# Final_Sch.net
KiCad netlist of a schematic drawn in EAGLE
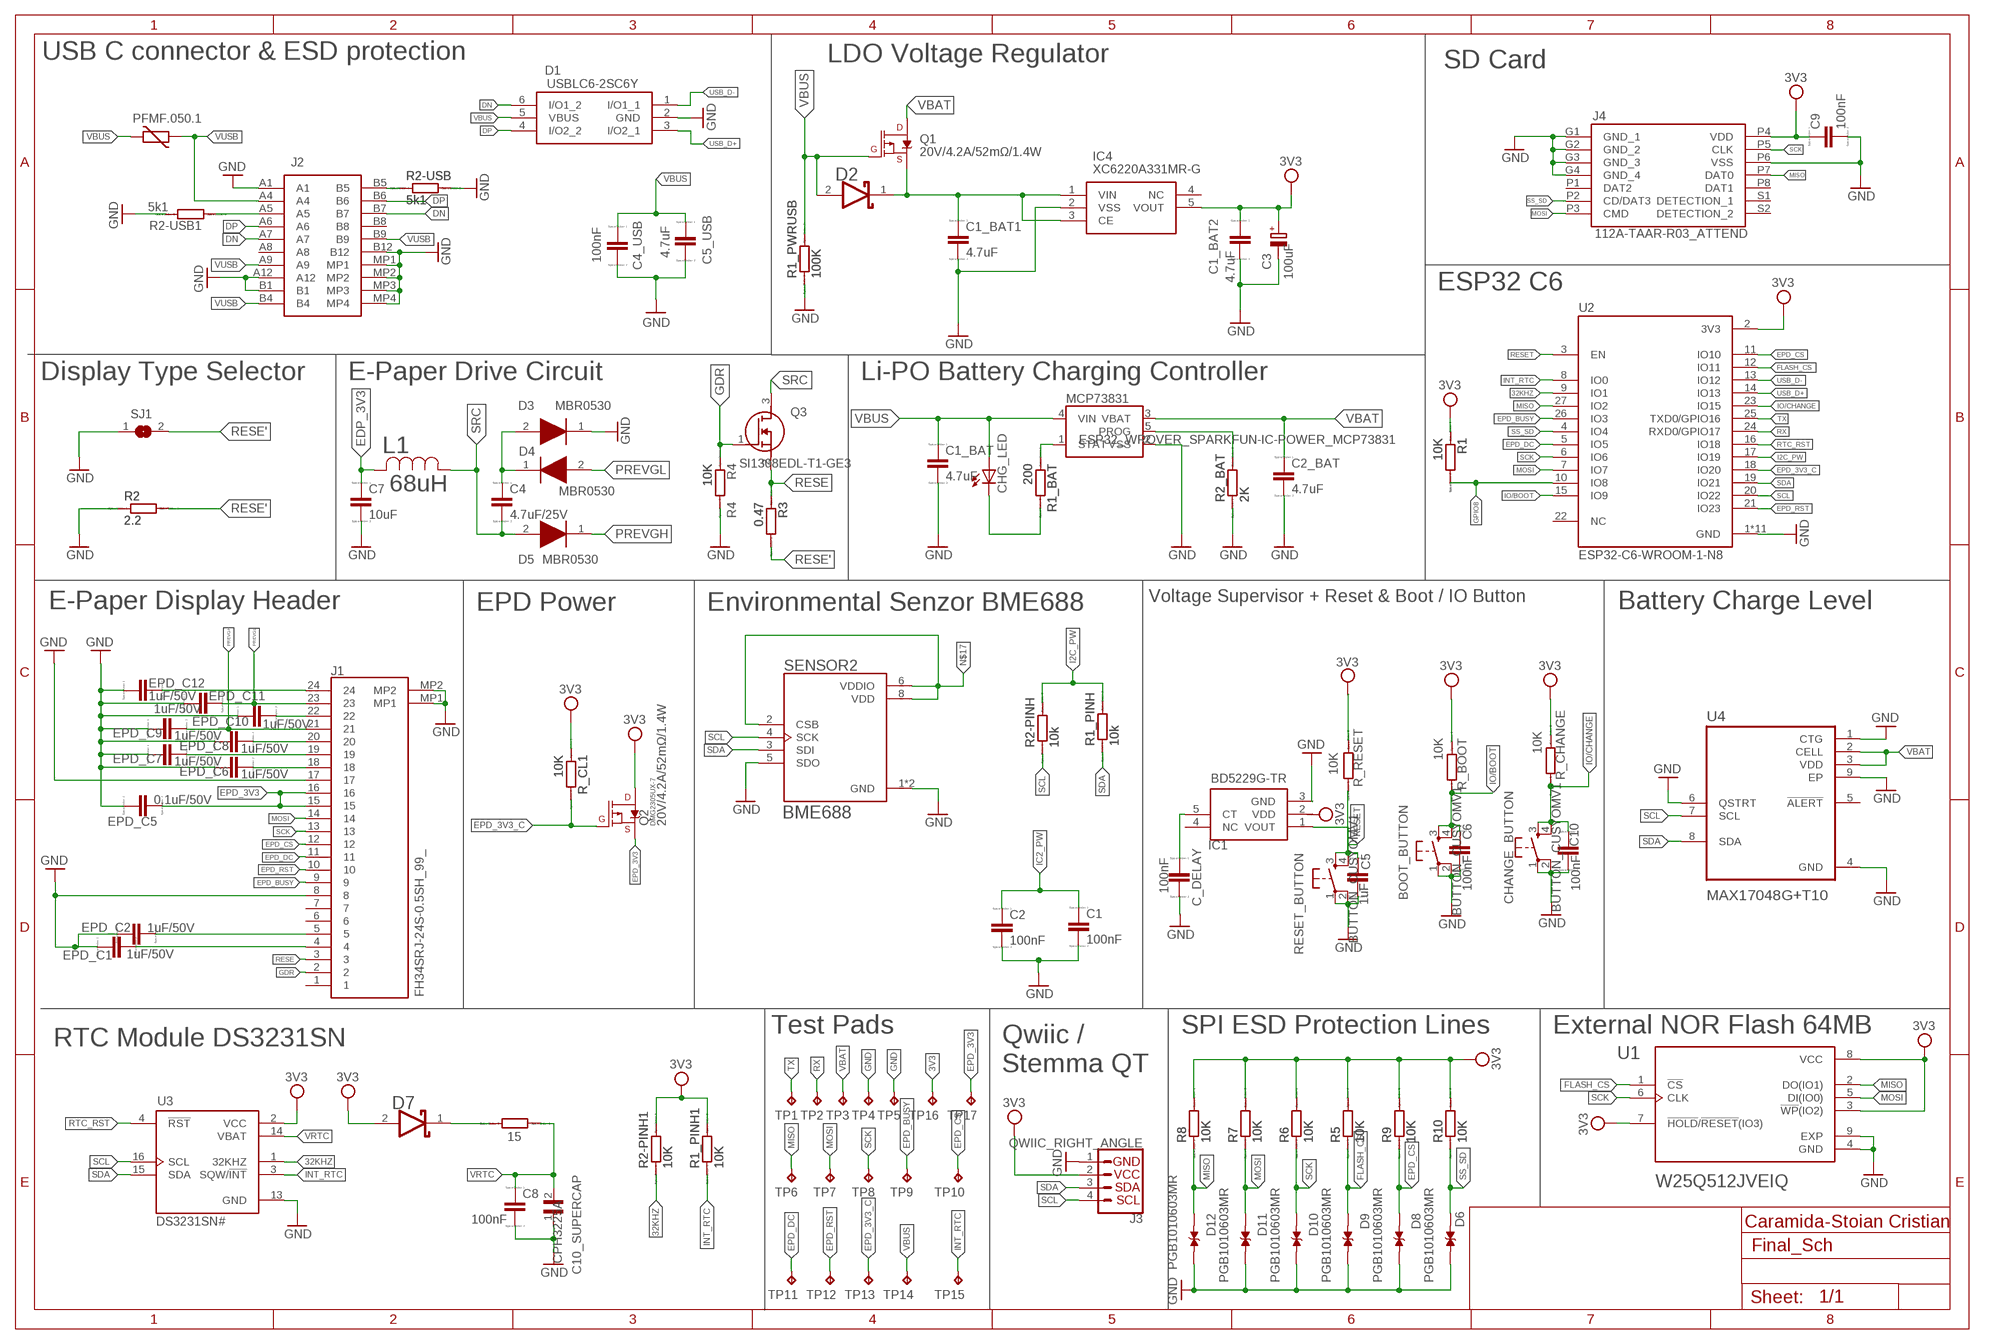
[diagram p0: schematic, sheet 1]

(export (version "E")
  (design (tool "Eeschema 10.0.6"))
  (components
    (comp (ref "BOOT_BUTTON")
      (value "BUTTON_CUSYOMV1")
      (footprint "eagle-import:MYBUTTON")
      (libsource (lib "eagle-import") (part "BUTTON_CUSYOMV1"))
    )
    (comp (ref "C1")
      (value "100nF")
      (footprint "eagle-import:ESP32_WROVER_EAGLE-LTSPICE_C0402")
      (libsource (lib "eagle-import") (part "ESP32_WROVER_EAGLE-LTSPICE_CC0402"))
    )
    (comp (ref "C1_BAT")
      (value "4.7uF")
      (footprint "eagle-import:ESP32_WROVER_EAGLE-LTSPICE_C0402")
      (libsource (lib "eagle-import") (part "ESP32_WROVER_EAGLE-LTSPICE_CC0402"))
    )
    (comp (ref "C1_BAT1")
      (value "4.7uF")
      (footprint "eagle-import:ESP32_WROVER_EAGLE-LTSPICE_C0402")
      (libsource (lib "eagle-import") (part "ESP32_WROVER_EAGLE-LTSPICE_CC0402"))
    )
    (comp (ref "C1_BAT2")
      (value "4.7uF")
      (footprint "eagle-import:ESP32_WROVER_EAGLE-LTSPICE_C0402")
      (libsource (lib "eagle-import") (part "ESP32_WROVER_EAGLE-LTSPICE_CC0402"))
    )
    (comp (ref "C2")
      (value "100nF")
      (footprint "eagle-import:ESP32_WROVER_EAGLE-LTSPICE_C0402")
      (libsource (lib "eagle-import") (part "ESP32_WROVER_EAGLE-LTSPICE_CC0402"))
    )
    (comp (ref "C2_BAT")
      (value "4.7uF")
      (footprint "eagle-import:ESP32_WROVER_EAGLE-LTSPICE_C0402")
      (libsource (lib "eagle-import") (part "ESP32_WROVER_EAGLE-LTSPICE_CC0402"))
    )
    (comp (ref "C3")
      (value "100uF")
      (footprint "eagle-import:RCL_CT3528")
      (libsource (lib "eagle-import") (part "RCL_CPOL-EUCT3528"))
    )
    (comp (ref "C4")
      (value "4.7uF/25V")
      (footprint "eagle-import:ESP32_WROVER_EAGLE-LTSPICE_C0402")
      (libsource (lib "eagle-import") (part "ESP32_WROVER_EAGLE-LTSPICE_CC0402"))
    )
    (comp (ref "C4_USB")
      (value "100nF")
      (footprint "eagle-import:ESP32_WROVER_EAGLE-LTSPICE_C0402")
      (libsource (lib "eagle-import") (part "ESP32_WROVER_EAGLE-LTSPICE_CC0402"))
    )
    (comp (ref "C5")
      (value "1uF")
      (footprint "eagle-import:EAGLE-LTSPICE_C0402")
      (libsource (lib "eagle-import") (part "EAGLE-LTSPICE_CC0402"))
    )
    (comp (ref "C5_USB")
      (value "4.7uF")
      (footprint "eagle-import:ESP32_WROVER_EAGLE-LTSPICE_C0402")
      (libsource (lib "eagle-import") (part "ESP32_WROVER_EAGLE-LTSPICE_CC0402"))
    )
    (comp (ref "C6")
      (value "100nF")
      (footprint "eagle-import:EAGLE-LTSPICE_C0402")
      (libsource (lib "eagle-import") (part "EAGLE-LTSPICE_CC0402"))
    )
    (comp (ref "C7")
      (value "10uF")
      (footprint "eagle-import:ESP32_WROVER_EAGLE-LTSPICE_C0402")
      (libsource (lib "eagle-import") (part "ESP32_WROVER_EAGLE-LTSPICE_CC0402"))
    )
    (comp (ref "C8")
      (value "100nF")
      (footprint "eagle-import:ESP32_WROVER_EAGLE-LTSPICE_C0402")
      (libsource (lib "eagle-import") (part "ESP32_WROVER_EAGLE-LTSPICE_CC0402"))
    )
    (comp (ref "C9")
      (value "100nF")
      (footprint "eagle-import:ESP32_WROVER_EAGLE-LTSPICE_C0402")
      (libsource (lib "eagle-import") (part "ESP32_WROVER_EAGLE-LTSPICE_CC0402"))
    )
    (comp (ref "C10")
      (value "100nF")
      (footprint "eagle-import:EAGLE-LTSPICE_C0402")
      (libsource (lib "eagle-import") (part "EAGLE-LTSPICE_CC0402"))
    )
    (comp (ref "C10_SUPERCAP")
      (value "CPH3225A")
      (footprint "eagle-import:CAPCP3225X100N")
      (fields (field (name "MF") "Seiko Instruments"))
      (libsource (lib "eagle-import") (part "CPH3225A"))
    )
    (comp (ref "CHANGE_BUTTON")
      (value "BUTTON_CUSYOMV1")
      (footprint "eagle-import:MYBUTTON")
      (libsource (lib "eagle-import") (part "BUTTON_CUSYOMV1"))
    )
    (comp (ref "CHG_LED")
      (value "ADAFRUIT_LEDCHIP-LED0603")
      (footprint "eagle-import:ADAFRUIT_CHIP-LED0603")
      (libsource (lib "eagle-import") (part "ADAFRUIT_LEDCHIP-LED0603"))
    )
    (comp (ref "C_DELAY")
      (value "100nF")
      (footprint "eagle-import:ESP32_WROVER_EAGLE-LTSPICE_C0402")
      (libsource (lib "eagle-import") (part "ESP32_WROVER_EAGLE-LTSPICE_CC0402"))
    )
    (comp (ref "D1")
      (value "USBLC6-2SC6Y")
      (footprint "eagle-import:SOT95P280X145-6N")
      (fields (field (name "MF") "STMicroelectronics"))
      (libsource (lib "eagle-import") (part "USBLC6-2SC6Y"))
    )
    (comp (ref "D2")
      (value "ESP32_WROVER_AVX---SD0805S020S1R0_AVX_SD0805S020S1R0_0_0AVX_SD0805S020S1R0_0_0")
      (footprint "eagle-import:ESP32_WROVER_AVX---SD0805S020S1R0_AVX_SD0805S020S1R0_0")
      (fields
        (field (name "DIGIKEY_PART_NUMBER") "478-7800-1-ND")
        (field (name "MF") "AVX")
        (field (name "MOUSER_PART_NUMBER") "581-SD0805S020S1R0")
      )
      (libsource (lib "eagle-import") (part "ESP32_WROVER_AVX---SD0805S020S1R0_AVX_SD0805S020S1R0_0_0AVX_SD0805S020S1R0_0_0"))
    )
    (comp (ref "D3")
      (value "MBR0530")
      (footprint "eagle-import:SOD3716X135N")
      (fields (field (name "MF") "ON Semiconductor"))
      (libsource (lib "eagle-import") (part "MBR0530"))
    )
    (comp (ref "D4")
      (value "MBR0530")
      (footprint "eagle-import:SOD3716X135N")
      (fields (field (name "MF") "ON Semiconductor"))
      (libsource (lib "eagle-import") (part "MBR0530"))
    )
    (comp (ref "D5")
      (value "MBR0530")
      (footprint "eagle-import:SOD3716X135N")
      (fields (field (name "MF") "ON Semiconductor"))
      (libsource (lib "eagle-import") (part "MBR0530"))
    )
    (comp (ref "D6")
      (value "PGB1010603MR")
      (footprint "eagle-import:DIOC1608X36N")
      (fields (field (name "MF") "Littelfuse Inc."))
      (libsource (lib "eagle-import") (part "PGB1010603MR"))
    )
    (comp (ref "D7")
      (value "ESP32_WROVER_AVX---SD0805S020S1R0_AVX_SD0805S020S1R0_0_0AVX_SD0805S020S1R0_0_0")
      (footprint "eagle-import:ESP32_WROVER_AVX---SD0805S020S1R0_AVX_SD0805S020S1R0_0")
      (fields
        (field (name "DIGIKEY_PART_NUMBER") "478-7800-1-ND")
        (field (name "MF") "AVX")
        (field (name "MOUSER_PART_NUMBER") "581-SD0805S020S1R0")
      )
      (libsource (lib "eagle-import") (part "ESP32_WROVER_AVX---SD0805S020S1R0_AVX_SD0805S020S1R0_0_0AVX_SD0805S020S1R0_0_0"))
    )
    (comp (ref "D8")
      (value "PGB1010603MR")
      (footprint "eagle-import:DIOC1608X36N")
      (fields (field (name "MF") "Littelfuse Inc."))
      (libsource (lib "eagle-import") (part "PGB1010603MR"))
    )
    (comp (ref "D9")
      (value "PGB1010603MR")
      (footprint "eagle-import:DIOC1608X36N")
      (fields (field (name "MF") "Littelfuse Inc."))
      (libsource (lib "eagle-import") (part "PGB1010603MR"))
    )
    (comp (ref "D10")
      (value "PGB1010603MR")
      (footprint "eagle-import:DIOC1608X36N")
      (fields (field (name "MF") "Littelfuse Inc."))
      (libsource (lib "eagle-import") (part "PGB1010603MR"))
    )
    (comp (ref "D11")
      (value "PGB1010603MR")
      (footprint "eagle-import:DIOC1608X36N")
      (fields (field (name "MF") "Littelfuse Inc."))
      (libsource (lib "eagle-import") (part "PGB1010603MR"))
    )
    (comp (ref "D12")
      (value "PGB1010603MR")
      (footprint "eagle-import:DIOC1608X36N")
      (fields (field (name "MF") "Littelfuse Inc."))
      (libsource (lib "eagle-import") (part "PGB1010603MR"))
    )
    (comp (ref "EPD_C1")
      (value "1uF/50V")
      (footprint "eagle-import:EAGLE-LTSPICE_C0402")
      (libsource (lib "eagle-import") (part "EAGLE-LTSPICE_CC0402"))
    )
    (comp (ref "EPD_C2")
      (value "1uF/50V")
      (footprint "eagle-import:EAGLE-LTSPICE_C0402")
      (libsource (lib "eagle-import") (part "EAGLE-LTSPICE_CC0402"))
    )
    (comp (ref "EPD_C5")
      (value "0.1uF/50V")
      (footprint "eagle-import:EAGLE-LTSPICE_C0402")
      (libsource (lib "eagle-import") (part "EAGLE-LTSPICE_CC0402"))
    )
    (comp (ref "EPD_C6")
      (value "1uF/50V")
      (footprint "eagle-import:EAGLE-LTSPICE_C0402")
      (libsource (lib "eagle-import") (part "EAGLE-LTSPICE_CC0402"))
    )
    (comp (ref "EPD_C7")
      (value "1uF/50V")
      (footprint "eagle-import:EAGLE-LTSPICE_C0402")
      (libsource (lib "eagle-import") (part "EAGLE-LTSPICE_CC0402"))
    )
    (comp (ref "EPD_C8")
      (value "1uF/50V")
      (footprint "eagle-import:EAGLE-LTSPICE_C0402")
      (libsource (lib "eagle-import") (part "EAGLE-LTSPICE_CC0402"))
    )
    (comp (ref "EPD_C9")
      (value "1uF/50V")
      (footprint "eagle-import:EAGLE-LTSPICE_C0402")
      (libsource (lib "eagle-import") (part "EAGLE-LTSPICE_CC0402"))
    )
    (comp (ref "EPD_C10")
      (value "1uF/50V")
      (footprint "eagle-import:EAGLE-LTSPICE_C0402")
      (libsource (lib "eagle-import") (part "EAGLE-LTSPICE_CC0402"))
    )
    (comp (ref "EPD_C11")
      (value "1uF/50V")
      (footprint "eagle-import:EAGLE-LTSPICE_C0402")
      (libsource (lib "eagle-import") (part "EAGLE-LTSPICE_CC0402"))
    )
    (comp (ref "EPD_C12")
      (value "1uF/50V")
      (footprint "eagle-import:EAGLE-LTSPICE_C0402")
      (libsource (lib "eagle-import") (part "EAGLE-LTSPICE_CC0402"))
    )
    (comp (ref "IC1")
      (value "BD5229G-TR")
      (footprint "eagle-import:SOT95P280X125-5N")
      (fields (field (name "MOUSER_PART_NUMBER") "755-BD5229G-TR"))
      (libsource (lib "eagle-import") (part "BD5229G-TR"))
    )
    (comp (ref "IC4")
      (value "XC6220A331MR-G")
      (footprint "eagle-import:SOT95P280X120-5N")
      (fields (field (name "MOUSER_PART_NUMBER") "865-XC6220A331MR-G"))
      (libsource (lib "eagle-import") (part "XC6220A331MR-G"))
    )
    (comp (ref "J1")
      (value "FH34SRJ-24S-0.5SH_99_")
      (footprint "eagle-import:FH34SRJ24S05SH99")
      (fields
        (field (name "MANUFACTURER_PART_NUMBER") "FH34SRJ-24S-0.5SH(99)")
        (field (name "MOUSER_PART_NUMBER") "798-FH34SRJ24S05SH99")
      )
      (libsource (lib "eagle-import") (part "FH34SRJ-24S-0.5SH_99_"))
    )
    (comp (ref "J2")
      (value "SAMACSYS_PARTS_USB4110-GF-A")
      (footprint "eagle-import:SAMACSYS_PARTS_USB4110GFA")
      (fields
        (field (name "MANUFACTURER_PART_NUMBER") "USB4110-GF-A")
        (field (name "MOUSER_PART_NUMBER") "640-USB4110-GF-A")
      )
      (libsource (lib "eagle-import") (part "SAMACSYS_PARTS_USB4110-GF-A"))
    )
    (comp (ref "J3")
      (value "QWIIC_RIGHT_ANGLE")
      (footprint "eagle-import:JST04_1MM_RA")
      (libsource (lib "eagle-import") (part "QWIIC_CONNECTORJS-1MM"))
    )
    (comp (ref "J4")
      (value "112A-TAAR-R03_ATTEND")
      (footprint "eagle-import:112ATAARR03ATTEND")
      (fields (field (name "MANUFACTURER_PART_NUMBER") "112A-TAAR-R03 ATTEND"))
      (libsource (lib "eagle-import") (part "112A-TAAR-R03_ATTEND"))
    )
    (comp (ref "L1")
      (value "68uH")
      (footprint "eagle-import:IND_4828-WE-TPC_WRE")
      (fields
        (field (name "MANUFACTURER_PART_NUMBER") "744043680")
        (field (name "COPYRIGHT") "Copyright (C) 2024 Ultra Librarian. All rights reserved.")
      )
      (libsource (lib "eagle-import") (part "744043680IND_4828-WE-TPC_WRE"))
    )
    (comp (ref "MCP73831")
      (value "ESP32_WROVER_SPARKFUN-IC-POWER_MCP73831")
      (footprint "eagle-import:ESP32_WROVER_SPARKFUN-IC-POWER_SOT23-5")
      (libsource (lib "eagle-import") (part "ESP32_WROVER_SPARKFUN-IC-POWER_MCP73831"))
    )
    (comp (ref "PFMF.050.1")
      (value "ESP32C6_VARISTORCN1812")
      (footprint "eagle-import:ESP32C6_VARISTOR_CT_CN1812")
      (libsource (lib "eagle-import") (part "ESP32C6_VARISTORCN1812"))
    )
    (comp (ref "Q1")
      (value "20V/4.2A/52mΩ/1.4W")
      (footprint "eagle-import:ESP32_WROVER_SPARKFUN-DISCRETESEMI_SOT23-3")
      (libsource (lib "eagle-import") (part "ESP32_WROVER_SPARKFUN-DISCRETESEMI_MOSFET_PCH-DMG2305UX-7"))
    )
    (comp (ref "Q2")
      (value "20V/4.2A/52mΩ/1.4W")
      (footprint "eagle-import:ESP32_WROVER_SPARKFUN-DISCRETESEMI_SOT23-3")
      (libsource (lib "eagle-import") (part "ESP32_WROVER_SPARKFUN-DISCRETESEMI_MOSFET_PCH-DMG2305UX-7"))
    )
    (comp (ref "Q3")
      (value "SI1308EDL-T1-GE3")
      (footprint "eagle-import:SOT65P210X110-3N")
      (fields (field (name "MF") "Vishay Siliconix"))
      (libsource (lib "eagle-import") (part "SI1308EDL-T1-GE3"))
    )
    (comp (ref "R1")
      (value "10K")
      (footprint "eagle-import:ESP32_WROVER_EAGLE-LTSPICE_R0402")
      (libsource (lib "eagle-import") (part "ESP32_WROVER_EAGLE-LTSPICE_RR0402"))
    )
    (comp (ref "R1_BAT")
      (value "200")
      (footprint "eagle-import:ESP32_WROVER_EAGLE-LTSPICE_R0402")
      (libsource (lib "eagle-import") (part "ESP32_WROVER_EAGLE-LTSPICE_RR0402"))
    )
    (comp (ref "R1_PINH")
      (value "10k")
      (footprint "eagle-import:ESP32_WROVER_EAGLE-LTSPICE_R0402")
      (libsource (lib "eagle-import") (part "ESP32_WROVER_EAGLE-LTSPICE_RR0402"))
    )
    (comp (ref "R1_PINH1")
      (value "10K")
      (footprint "eagle-import:ESP32_WROVER_EAGLE-LTSPICE_R0402")
      (libsource (lib "eagle-import") (part "ESP32_WROVER_EAGLE-LTSPICE_RR0402"))
    )
    (comp (ref "R1_PWRUSB")
      (value "100K")
      (footprint "eagle-import:ESP32_WROVER_EAGLE-LTSPICE_R0402")
      (libsource (lib "eagle-import") (part "ESP32_WROVER_EAGLE-LTSPICE_RR0402"))
    )
    (comp (ref "R2")
      (value "2.2")
      (footprint "eagle-import:ESP32_WROVER_EAGLE-LTSPICE_R0402")
      (libsource (lib "eagle-import") (part "ESP32_WROVER_EAGLE-LTSPICE_RR0402"))
    )
    (comp (ref "R2-PINH")
      (value "10k")
      (footprint "eagle-import:ESP32_WROVER_EAGLE-LTSPICE_R0402")
      (libsource (lib "eagle-import") (part "ESP32_WROVER_EAGLE-LTSPICE_RR0402"))
    )
    (comp (ref "R2-PINH1")
      (value "10K")
      (footprint "eagle-import:ESP32_WROVER_EAGLE-LTSPICE_R0402")
      (libsource (lib "eagle-import") (part "ESP32_WROVER_EAGLE-LTSPICE_RR0402"))
    )
    (comp (ref "R2-USB")
      (value "5k1")
      (footprint "eagle-import:ESP32_WROVER_EAGLE-LTSPICE_R0402")
      (libsource (lib "eagle-import") (part "ESP32_WROVER_EAGLE-LTSPICE_RR0402"))
    )
    (comp (ref "R2-USB1")
      (value "5k1")
      (footprint "eagle-import:ESP32_WROVER_EAGLE-LTSPICE_R0402")
      (libsource (lib "eagle-import") (part "ESP32_WROVER_EAGLE-LTSPICE_RR0402"))
    )
    (comp (ref "R2_BAT")
      (value "2K")
      (footprint "eagle-import:ESP32_WROVER_EAGLE-LTSPICE_R0402")
      (libsource (lib "eagle-import") (part "ESP32_WROVER_EAGLE-LTSPICE_RR0402"))
    )
    (comp (ref "R3")
      (value "0.47")
      (footprint "eagle-import:ESP32_WROVER_EAGLE-LTSPICE_R0402")
      (libsource (lib "eagle-import") (part "ESP32_WROVER_EAGLE-LTSPICE_RR0402"))
    )
    (comp (ref "R4")
      (value "10K")
      (footprint "eagle-import:ESP32_WROVER_EAGLE-LTSPICE_R0402")
      (libsource (lib "eagle-import") (part "ESP32_WROVER_EAGLE-LTSPICE_RR0402"))
    )
    (comp (ref "R5")
      (value "10K")
      (footprint "eagle-import:ESP32_WROVER_EAGLE-LTSPICE_R0402")
      (libsource (lib "eagle-import") (part "ESP32_WROVER_EAGLE-LTSPICE_RR0402"))
    )
    (comp (ref "R6")
      (value "10K")
      (footprint "eagle-import:ESP32_WROVER_EAGLE-LTSPICE_R0402")
      (libsource (lib "eagle-import") (part "ESP32_WROVER_EAGLE-LTSPICE_RR0402"))
    )
    (comp (ref "R7")
      (value "10K")
      (footprint "eagle-import:ESP32_WROVER_EAGLE-LTSPICE_R0402")
      (libsource (lib "eagle-import") (part "ESP32_WROVER_EAGLE-LTSPICE_RR0402"))
    )
    (comp (ref "R8")
      (value "10K")
      (footprint "eagle-import:ESP32_WROVER_EAGLE-LTSPICE_R0402")
      (libsource (lib "eagle-import") (part "ESP32_WROVER_EAGLE-LTSPICE_RR0402"))
    )
    (comp (ref "R9")
      (value "10K")
      (footprint "eagle-import:ESP32_WROVER_EAGLE-LTSPICE_R0402")
      (libsource (lib "eagle-import") (part "ESP32_WROVER_EAGLE-LTSPICE_RR0402"))
    )
    (comp (ref "R10")
      (value "10K")
      (footprint "eagle-import:ESP32_WROVER_EAGLE-LTSPICE_R0402")
      (libsource (lib "eagle-import") (part "ESP32_WROVER_EAGLE-LTSPICE_RR0402"))
    )
    (comp (ref "RESET_BUTTON")
      (value "BUTTON_CUSYOMV1")
      (footprint "eagle-import:MYBUTTON")
      (libsource (lib "eagle-import") (part "BUTTON_CUSYOMV1"))
    )
    (comp (ref "R_BOOT")
      (value "10K")
      (footprint "eagle-import:ESP32_WROVER_EAGLE-LTSPICE_R0402")
      (libsource (lib "eagle-import") (part "ESP32_WROVER_EAGLE-LTSPICE_RR0402"))
    )
    (comp (ref "R_CAPACITOR")
      (value "15")
      (footprint "eagle-import:ESP32_WROVER_EAGLE-LTSPICE_R0402")
      (libsource (lib "eagle-import") (part "ESP32_WROVER_EAGLE-LTSPICE_RR0402"))
    )
    (comp (ref "R_CHANGE")
      (value "10K")
      (footprint "eagle-import:ESP32_WROVER_EAGLE-LTSPICE_R0402")
      (libsource (lib "eagle-import") (part "ESP32_WROVER_EAGLE-LTSPICE_RR0402"))
    )
    (comp (ref "R_CL1")
      (value "10K")
      (footprint "eagle-import:ESP32_WROVER_EAGLE-LTSPICE_R0402")
      (libsource (lib "eagle-import") (part "ESP32_WROVER_EAGLE-LTSPICE_RR0402"))
    )
    (comp (ref "R_RESET")
      (value "10K")
      (footprint "eagle-import:ESP32_WROVER_EAGLE-LTSPICE_R0402")
      (libsource (lib "eagle-import") (part "ESP32_WROVER_EAGLE-LTSPICE_RR0402"))
    )
    (comp (ref "SENSOR2")
      (value "ESP32_WROVER_BME680_BME680")
      (footprint "eagle-import:ESP32_WROVER_BME680_PSON80P300X300X100-8N")
      (fields (field (name "MF") "Bosch Sensortec") (field (name "MP") "BME680"))
      (libsource (lib "eagle-import") (part "ESP32_WROVER_BME680_BME680"))
    )
    (comp (ref "SJ1") (value "SJ") (footprint "eagle-import:SJ") (libsource (lib "eagle-import") (part "SJ")))
    (comp (ref "TP1")
      (value "TPTP20R")
      (footprint "eagle-import:TP20R")
      (libsource (lib "eagle-import") (part "TPTP20R"))
    )
    (comp (ref "TP2")
      (value "TPTP20R")
      (footprint "eagle-import:TP20R")
      (libsource (lib "eagle-import") (part "TPTP20R"))
    )
    (comp (ref "TP3")
      (value "TPTP20R")
      (footprint "eagle-import:TP20R")
      (libsource (lib "eagle-import") (part "TPTP20R"))
    )
    (comp (ref "TP4")
      (value "TPTP20R")
      (footprint "eagle-import:TP20R")
      (libsource (lib "eagle-import") (part "TPTP20R"))
    )
    (comp (ref "TP5")
      (value "TPTP20R")
      (footprint "eagle-import:TP20R")
      (libsource (lib "eagle-import") (part "TPTP20R"))
    )
    (comp (ref "TP6")
      (value "TPTP20R")
      (footprint "eagle-import:TP20R")
      (libsource (lib "eagle-import") (part "TPTP20R"))
    )
    (comp (ref "TP7")
      (value "TPTP20R")
      (footprint "eagle-import:TP20R")
      (libsource (lib "eagle-import") (part "TPTP20R"))
    )
    (comp (ref "TP8")
      (value "TPTP20R")
      (footprint "eagle-import:TP20R")
      (libsource (lib "eagle-import") (part "TPTP20R"))
    )
    (comp (ref "TP9")
      (value "TPTP20R")
      (footprint "eagle-import:TP20R")
      (libsource (lib "eagle-import") (part "TPTP20R"))
    )
    (comp (ref "TP10")
      (value "TPTP20R")
      (footprint "eagle-import:TP20R")
      (libsource (lib "eagle-import") (part "TPTP20R"))
    )
    (comp (ref "TP11")
      (value "TPTP20R")
      (footprint "eagle-import:TP20R")
      (libsource (lib "eagle-import") (part "TPTP20R"))
    )
    (comp (ref "TP12")
      (value "TPTP20R")
      (footprint "eagle-import:TP20R")
      (libsource (lib "eagle-import") (part "TPTP20R"))
    )
    (comp (ref "TP13")
      (value "TPTP20R")
      (footprint "eagle-import:TP20R")
      (libsource (lib "eagle-import") (part "TPTP20R"))
    )
    (comp (ref "TP14")
      (value "TPTP20R")
      (footprint "eagle-import:TP20R")
      (libsource (lib "eagle-import") (part "TPTP20R"))
    )
    (comp (ref "TP15")
      (value "TPTP20R")
      (footprint "eagle-import:TP20R")
      (libsource (lib "eagle-import") (part "TPTP20R"))
    )
    (comp (ref "TP16")
      (value "TPTP20R")
      (footprint "eagle-import:TP20R")
      (libsource (lib "eagle-import") (part "TPTP20R"))
    )
    (comp (ref "TP17")
      (value "TPTP20R")
      (footprint "eagle-import:TP20R")
      (libsource (lib "eagle-import") (part "TPTP20R"))
    )
    (comp (ref "U1")
      (value "W25Q512JVEIQ")
      (footprint "eagle-import:SON127P600X800X80-9N")
      (fields (field (name "MF") "Winbond Electronics"))
      (libsource (lib "eagle-import") (part "W25Q512JVEIQ"))
    )
    (comp (ref "U2")
      (value "ESP32-C6-WROOM-1-N8")
      (footprint "eagle-import:XCVR_ESP32-C6-WROOM-1-N8")
      (fields (field (name "MF") "Espressif Systems"))
      (libsource (lib "eagle-import") (part "ESP32-C6-WROOM-1-N8"))
    )
    (comp (ref "U3")
      (value "DS3231SN#")
      (footprint "eagle-import:SOIC127P1032X265-16N")
      (fields (field (name "MF") "Analog Devices"))
      (libsource (lib "eagle-import") (part "DS3231SN#"))
    )
    (comp (ref "U4")
      (value "MAX17048G+T10")
      (footprint "eagle-import:SON50P200X200X80-9N")
      (fields (field (name "MF") "Analog Devices"))
      (libsource (lib "eagle-import") (part "MAX17048G+T10"))
    )
  )
  (nets
    (net (code "1") (name "3V3") (class "Default")
      (node (ref "C1_BAT2") (pin "1") (pinfunction "1_1") (pintype "passive"))
      (node (ref "C3") (pin "+") (pinfunction "+_+") (pintype "passive"))
      (node (ref "C9") (pin "1") (pinfunction "1_1") (pintype "passive"))
      (node (ref "D7") (pin "2") (pinfunction "ANODE_2") (pintype "bidirectional"))
      (node (ref "IC4") (pin "5") (pinfunction "VOUT_5") (pintype "bidirectional"))
      (node (ref "J3") (pin "2") (pinfunction "2_2") (pintype "power_in"))
      (node (ref "J4") (pin "P4") (pinfunction "VDD_P4") (pintype "bidirectional"))
      (node (ref "Q2") (pin "3") (pinfunction "D_3") (pintype "bidirectional"))
      (node (ref "R1") (pin "1") (pinfunction "1_1") (pintype "passive"))
      (node (ref "R10") (pin "2") (pinfunction "2_2") (pintype "passive"))
      (node (ref "R1_PINH1") (pin "2") (pinfunction "2_2") (pintype "passive"))
      (node (ref "R2-PINH1") (pin "2") (pinfunction "2_2") (pintype "passive"))
      (node (ref "R5") (pin "2") (pinfunction "2_2") (pintype "passive"))
      (node (ref "R6") (pin "2") (pinfunction "2_2") (pintype "passive"))
      (node (ref "R7") (pin "2") (pinfunction "2_2") (pintype "passive"))
      (node (ref "R8") (pin "2") (pinfunction "2_2") (pintype "passive"))
      (node (ref "R9") (pin "2") (pinfunction "2_2") (pintype "passive"))
      (node (ref "R_BOOT") (pin "2") (pinfunction "2_2") (pintype "passive"))
      (node (ref "R_CHANGE") (pin "2") (pinfunction "2_2") (pintype "passive"))
      (node (ref "R_CL1") (pin "1") (pinfunction "1_1") (pintype "passive"))
      (node (ref "R_RESET") (pin "2") (pinfunction "2_2") (pintype "passive"))
      (node (ref "TP16") (pin "TP") (pinfunction "TP_TP") (pintype "input"))
      (node (ref "U1") (pin "3") (pinfunction "~{WP}(IO2)_3") (pintype "bidirectional"))
      (node (ref "U1") (pin "7") (pinfunction "~{HOLD}/~{RESET}(IO3)_7") (pintype "bidirectional"))
      (node (ref "U1") (pin "8") (pinfunction "VCC_8") (pintype "power_in"))
      (node (ref "U2") (pin "2") (pinfunction "3V3_2") (pintype "power_in"))
      (node (ref "U3") (pin "2") (pinfunction "VCC_2") (pintype "power_in"))
    )
    (net (code "2") (name "32KHZ") (class "Default")
      (node (ref "R2-PINH1") (pin "1") (pinfunction "1_1") (pintype "passive"))
      (node (ref "U2") (pin "9") (pinfunction "IO1_9") (pintype "bidirectional"))
      (node (ref "U3") (pin "1") (pinfunction "32KHZ_1") (pintype "output"))
    )
    (net (code "3") (name "DN") (class "Default")
      (node (ref "D1") (pin "6") (pinfunction "I/O1_2_6") (pintype "bidirectional"))
      (node (ref "J2") (pin "A7") (pinfunction "A7_A7") (pintype "bidirectional"))
      (node (ref "J2") (pin "B7") (pinfunction "B7_B7") (pintype "bidirectional"))
    )
    (net (code "4") (name "DP") (class "Default")
      (node (ref "D1") (pin "4") (pinfunction "I/O2_2_4") (pintype "bidirectional"))
      (node (ref "J2") (pin "A6") (pinfunction "A6_A6") (pintype "bidirectional"))
      (node (ref "J2") (pin "B6") (pinfunction "B6_B6") (pintype "bidirectional"))
    )
    (net (code "5") (name "EDP_3V3") (class "Default")
      (node (ref "C7") (pin "1") (pinfunction "1_1") (pintype "passive"))
      (node (ref "L1") (pin "2") (pinfunction "2_2") (pintype "passive"))
    )
    (net (code "6") (name "EPD_3V3") (class "Default")
      (node (ref "EPD_C5") (pin "2") (pinfunction "2_2") (pintype "passive"))
      (node (ref "J1") (pin "15") (pinfunction "15_15") (pintype "bidirectional"))
      (node (ref "J1") (pin "16") (pinfunction "16_16") (pintype "bidirectional"))
      (node (ref "Q2") (pin "2") (pinfunction "S_2") (pintype "bidirectional"))
      (node (ref "TP17") (pin "TP") (pinfunction "TP_TP") (pintype "input"))
    )
    (net (code "7") (name "EPD_3V3_C") (class "Default")
      (node (ref "Q2") (pin "1") (pinfunction "G_1") (pintype "bidirectional"))
      (node (ref "R_CL1") (pin "2") (pinfunction "2_2") (pintype "passive"))
      (node (ref "TP13") (pin "TP") (pinfunction "TP_TP") (pintype "input"))
      (node (ref "U2") (pin "18") (pinfunction "IO20_18") (pintype "bidirectional"))
    )
    (net (code "8") (name "EPD_BUSY") (class "Default")
      (node (ref "J1") (pin "9") (pinfunction "9_9") (pintype "bidirectional"))
      (node (ref "TP9") (pin "TP") (pinfunction "TP_TP") (pintype "input"))
      (node (ref "U2") (pin "26") (pinfunction "IO3_26") (pintype "bidirectional"))
    )
    (net (code "9") (name "EPD_CS") (class "Default")
      (node (ref "D8") (pin "1") (pinfunction "1_1") (pintype "passive"))
      (node (ref "J1") (pin "12") (pinfunction "12_12") (pintype "bidirectional"))
      (node (ref "R9") (pin "1") (pinfunction "1_1") (pintype "passive"))
      (node (ref "TP10") (pin "TP") (pinfunction "TP_TP") (pintype "input"))
      (node (ref "U2") (pin "11") (pinfunction "IO10_11") (pintype "bidirectional"))
    )
    (net (code "10") (name "EPD_DC") (class "Default")
      (node (ref "J1") (pin "11") (pinfunction "11_11") (pintype "bidirectional"))
      (node (ref "TP11") (pin "TP") (pinfunction "TP_TP") (pintype "input"))
      (node (ref "U2") (pin "5") (pinfunction "IO5_5") (pintype "bidirectional"))
    )
    (net (code "11") (name "EPD_RST") (class "Default")
      (node (ref "J1") (pin "10") (pinfunction "10_10") (pintype "bidirectional"))
      (node (ref "TP12") (pin "TP") (pinfunction "TP_TP") (pintype "input"))
      (node (ref "U2") (pin "21") (pinfunction "IO23_21") (pintype "bidirectional"))
    )
    (net (code "12") (name "FLASH_CS") (class "Default")
      (node (ref "D9") (pin "1") (pinfunction "1_1") (pintype "passive"))
      (node (ref "R5") (pin "1") (pinfunction "1_1") (pintype "passive"))
      (node (ref "U1") (pin "1") (pinfunction "~{CS}_1") (pintype "input"))
      (node (ref "U2") (pin "12") (pinfunction "IO11_12") (pintype "bidirectional"))
    )
    (net (code "13") (name "GDR") (class "Default")
      (node (ref "J1") (pin "2") (pinfunction "2_2") (pintype "bidirectional"))
      (node (ref "Q3") (pin "1") (pinfunction "G_1") (pintype "bidirectional"))
      (node (ref "R4") (pin "1") (pinfunction "1_1") (pintype "passive"))
    )
    (net (code "14") (name "GND") (class "Default")
      (node (ref "BOOT_BUTTON") (pin "1") (pinfunction "1_1") (pintype "passive"))
      (node (ref "BOOT_BUTTON") (pin "2") (pinfunction "2_2") (pintype "passive"))
      (node (ref "C1") (pin "2") (pinfunction "2_2") (pintype "passive"))
      (node (ref "C10") (pin "2") (pinfunction "2_2") (pintype "passive"))
      (node (ref "C10_SUPERCAP") (pin "1") (pinfunction "1_1") (pintype "passive"))
      (node (ref "C1_BAT") (pin "2") (pinfunction "2_2") (pintype "passive"))
      (node (ref "C1_BAT1") (pin "2") (pinfunction "2_2") (pintype "passive"))
      (node (ref "C1_BAT2") (pin "2") (pinfunction "2_2") (pintype "passive"))
      (node (ref "C2") (pin "2") (pinfunction "2_2") (pintype "passive"))
      (node (ref "C2_BAT") (pin "2") (pinfunction "2_2") (pintype "passive"))
      (node (ref "C3") (pin "-") (pinfunction "-_-") (pintype "passive"))
      (node (ref "C4_USB") (pin "2") (pinfunction "2_2") (pintype "passive"))
      (node (ref "C5") (pin "2") (pinfunction "2_2") (pintype "passive"))
      (node (ref "C5_USB") (pin "2") (pinfunction "2_2") (pintype "passive"))
      (node (ref "C6") (pin "2") (pinfunction "2_2") (pintype "passive"))
      (node (ref "C7") (pin "2") (pinfunction "2_2") (pintype "passive"))
      (node (ref "C8") (pin "2") (pinfunction "2_2") (pintype "passive"))
      (node (ref "C9") (pin "2") (pinfunction "2_2") (pintype "passive"))
      (node (ref "CHANGE_BUTTON") (pin "1") (pinfunction "1_1") (pintype "passive"))
      (node (ref "CHANGE_BUTTON") (pin "2") (pinfunction "2_2") (pintype "passive"))
      (node (ref "C_DELAY") (pin "2") (pinfunction "2_2") (pintype "passive"))
      (node (ref "D1") (pin "2") (pinfunction "GND_2") (pintype "bidirectional"))
      (node (ref "D10") (pin "2") (pinfunction "2_2") (pintype "passive"))
      (node (ref "D11") (pin "2") (pinfunction "2_2") (pintype "passive"))
      (node (ref "D12") (pin "2") (pinfunction "2_2") (pintype "passive"))
      (node (ref "D3") (pin "1") (pinfunction "K_1") (pintype "bidirectional"))
      (node (ref "D6") (pin "2") (pinfunction "2_2") (pintype "passive"))
      (node (ref "D8") (pin "2") (pinfunction "2_2") (pintype "passive"))
      (node (ref "D9") (pin "2") (pinfunction "2_2") (pintype "passive"))
      (node (ref "EPD_C1") (pin "1") (pinfunction "1_1") (pintype "passive"))
      (node (ref "EPD_C10") (pin "1") (pinfunction "1_1") (pintype "passive"))
      (node (ref "EPD_C11") (pin "1") (pinfunction "1_1") (pintype "passive"))
      (node (ref "EPD_C12") (pin "1") (pinfunction "1_1") (pintype "passive"))
      (node (ref "EPD_C2") (pin "1") (pinfunction "1_1") (pintype "passive"))
      (node (ref "EPD_C5") (pin "1") (pinfunction "1_1") (pintype "passive"))
      (node (ref "EPD_C6") (pin "1") (pinfunction "1_1") (pintype "passive"))
      (node (ref "EPD_C7") (pin "1") (pinfunction "1_1") (pintype "passive"))
      (node (ref "EPD_C8") (pin "1") (pinfunction "1_1") (pintype "passive"))
      (node (ref "EPD_C9") (pin "1") (pinfunction "1_1") (pintype "passive"))
      (node (ref "IC1") (pin "3") (pinfunction "GND_3") (pintype "bidirectional"))
      (node (ref "IC4") (pin "2") (pinfunction "VSS_2") (pintype "bidirectional"))
      (node (ref "J1") (pin "17") (pinfunction "17_17") (pintype "bidirectional"))
      (node (ref "J1") (pin "8") (pinfunction "8_8") (pintype "bidirectional"))
      (node (ref "J1") (pin "MP1") (pinfunction "MP1_MP1") (pintype "bidirectional"))
      (node (ref "J1") (pin "MP2") (pinfunction "MP2_MP2") (pintype "bidirectional"))
      (node (ref "J2") (pin "A1") (pinfunction "A1_A1") (pintype "bidirectional"))
      (node (ref "J2") (pin "A12") (pinfunction "A12_A12") (pintype "bidirectional"))
      (node (ref "J2") (pin "B1") (pinfunction "B1_B1") (pintype "bidirectional"))
      (node (ref "J2") (pin "B12") (pinfunction "B12_B12") (pintype "bidirectional"))
      (node (ref "J2") (pin "MP1") (pinfunction "MP1_MP1") (pintype "bidirectional"))
      (node (ref "J2") (pin "MP2") (pinfunction "MP2_MP2") (pintype "bidirectional"))
      (node (ref "J2") (pin "MP3") (pinfunction "MP3_MP3") (pintype "bidirectional"))
      (node (ref "J2") (pin "MP4") (pinfunction "MP4_MP4") (pintype "bidirectional"))
      (node (ref "J3") (pin "1") (pinfunction "1_1") (pintype "power_in"))
      (node (ref "J4") (pin "G1") (pinfunction "GND_1_G1") (pintype "bidirectional"))
      (node (ref "J4") (pin "G2") (pinfunction "GND_2_G2") (pintype "bidirectional"))
      (node (ref "J4") (pin "G3") (pinfunction "GND_3_G3") (pintype "bidirectional"))
      (node (ref "J4") (pin "G4") (pinfunction "GND_4_G4") (pintype "bidirectional"))
      (node (ref "J4") (pin "P6") (pinfunction "VSS_P6") (pintype "bidirectional"))
      (node (ref "MCP73831") (pin "2") (pinfunction "VSS_2") (pintype "power_in"))
      (node (ref "R1_PWRUSB") (pin "1") (pinfunction "1_1") (pintype "passive"))
      (node (ref "R2") (pin "1") (pinfunction "1_1") (pintype "passive"))
      (node (ref "R2-USB") (pin "2") (pinfunction "2_2") (pintype "passive"))
      (node (ref "R2-USB1") (pin "1") (pinfunction "1_1") (pintype "passive"))
      (node (ref "R2_BAT") (pin "1") (pinfunction "1_1") (pintype "passive"))
      (node (ref "R4") (pin "2") (pinfunction "2_2") (pintype "passive"))
      (node (ref "RESET_BUTTON") (pin "1") (pinfunction "1_1") (pintype "passive"))
      (node (ref "RESET_BUTTON") (pin "2") (pinfunction "2_2") (pintype "passive"))
      (node (ref "SENSOR2") (pin "1") (pinfunction "GND_1") (pintype "power_in"))
      (node (ref "SENSOR2") (pin "5") (pinfunction "SDO_5") (pintype "bidirectional"))
      (node (ref "SENSOR2") (pin "7") (pinfunction "GND_7") (pintype "power_in"))
      (node (ref "SJ1") (pin "1") (pinfunction "1_1") (pintype "passive"))
      (node (ref "TP4") (pin "TP") (pinfunction "TP_TP") (pintype "input"))
      (node (ref "TP5") (pin "TP") (pinfunction "TP_TP") (pintype "input"))
      (node (ref "U1") (pin "4") (pinfunction "GND_4") (pintype "power_in"))
      (node (ref "U1") (pin "9") (pinfunction "EXP_9") (pintype "passive"))
      (node (ref "U2") (pin "1") (pinfunction "GND_1") (pintype "power_in"))
      (node (ref "U2") (pin "28") (pinfunction "GND_28") (pintype "power_in"))
      (node (ref "U2") (pin "29_1") (pinfunction "GND_29_1") (pintype "power_in"))
      (node (ref "U2") (pin "29_2") (pinfunction "GND_29_2") (pintype "power_in"))
      (node (ref "U2") (pin "29_3") (pinfunction "GND_29_3") (pintype "power_in"))
      (node (ref "U2") (pin "29_4") (pinfunction "GND_29_4") (pintype "power_in"))
      (node (ref "U2") (pin "29_5") (pinfunction "GND_29_5") (pintype "power_in"))
      (node (ref "U2") (pin "29_6") (pinfunction "GND_29_6") (pintype "power_in"))
      (node (ref "U2") (pin "29_7") (pinfunction "GND_29_7") (pintype "power_in"))
      (node (ref "U2") (pin "29_8") (pinfunction "GND_29_8") (pintype "power_in"))
      (node (ref "U2") (pin "29_9") (pinfunction "GND_29_9") (pintype "power_in"))
      (node (ref "U3") (pin "13") (pinfunction "GND_13") (pintype "power_in"))
      (node (ref "U4") (pin "1") (pinfunction "CTG_1") (pintype "power_in"))
      (node (ref "U4") (pin "4") (pinfunction "GND_4") (pintype "power_in"))
      (node (ref "U4") (pin "6") (pinfunction "QSTRT_6") (pintype "input"))
      (node (ref "U4") (pin "9") (pinfunction "EP_9") (pintype "power_in"))
    )
    (net (code "15") (name "GPIO8") (class "Default")
      (node (ref "R1") (pin "2") (pinfunction "2_2") (pintype "passive"))
      (node (ref "U2") (pin "10") (pinfunction "IO8_10") (pintype "bidirectional"))
    )
    (net (code "16") (name "I2C_PW") (class "Default")
      (node (ref "R1_PINH") (pin "2") (pinfunction "2_2") (pintype "passive"))
      (node (ref "R2-PINH") (pin "2") (pinfunction "2_2") (pintype "passive"))
      (node (ref "U2") (pin "17") (pinfunction "IO19_17") (pintype "bidirectional"))
    )
    (net (code "17") (name "IC2_PW") (class "Default")
      (node (ref "C1") (pin "1") (pinfunction "1_1") (pintype "passive"))
      (node (ref "C2") (pin "1") (pinfunction "1_1") (pintype "passive"))
    )
    (net (code "18") (name "INT_RTC") (class "Default")
      (node (ref "R1_PINH1") (pin "1") (pinfunction "1_1") (pintype "passive"))
      (node (ref "TP15") (pin "TP") (pinfunction "TP_TP") (pintype "input"))
      (node (ref "U2") (pin "8") (pinfunction "IO0_8") (pintype "bidirectional"))
      (node (ref "U3") (pin "3") (pinfunction "SQW/~{INT}_3") (pintype "output"))
    )
    (net (code "19") (name "IO{slash}BOOT") (class "Default")
      (node (ref "BOOT_BUTTON") (pin "3") (pinfunction "3_3") (pintype "passive"))
      (node (ref "BOOT_BUTTON") (pin "4") (pinfunction "4_4") (pintype "passive"))
      (node (ref "C6") (pin "1") (pinfunction "1_1") (pintype "passive"))
      (node (ref "R_BOOT") (pin "1") (pinfunction "1_1") (pintype "passive"))
      (node (ref "U2") (pin "15") (pinfunction "IO9_15") (pintype "bidirectional"))
    )
    (net (code "20") (name "IO{slash}CHANGE") (class "Default")
      (node (ref "C10") (pin "1") (pinfunction "1_1") (pintype "passive"))
      (node (ref "CHANGE_BUTTON") (pin "3") (pinfunction "3_3") (pintype "passive"))
      (node (ref "CHANGE_BUTTON") (pin "4") (pinfunction "4_4") (pintype "passive"))
      (node (ref "R_CHANGE") (pin "1") (pinfunction "1_1") (pintype "passive"))
      (node (ref "U2") (pin "23") (pinfunction "IO15_23") (pintype "bidirectional"))
    )
    (net (code "21") (name "MISO") (class "Default")
      (node (ref "D12") (pin "1") (pinfunction "1_1") (pintype "passive"))
      (node (ref "J4") (pin "P7") (pinfunction "DAT0_P7") (pintype "bidirectional"))
      (node (ref "R8") (pin "1") (pinfunction "1_1") (pintype "passive"))
      (node (ref "TP6") (pin "TP") (pinfunction "TP_TP") (pintype "input"))
      (node (ref "U1") (pin "2") (pinfunction "DO(IO1)_2") (pintype "bidirectional"))
      (node (ref "U2") (pin "27") (pinfunction "IO2_27") (pintype "bidirectional"))
    )
    (net (code "22") (name "MOSI") (class "Default")
      (node (ref "D11") (pin "1") (pinfunction "1_1") (pintype "passive"))
      (node (ref "J1") (pin "14") (pinfunction "14_14") (pintype "bidirectional"))
      (node (ref "J4") (pin "P3") (pinfunction "CMD_P3") (pintype "bidirectional"))
      (node (ref "R7") (pin "1") (pinfunction "1_1") (pintype "passive"))
      (node (ref "TP7") (pin "TP") (pinfunction "TP_TP") (pintype "input"))
      (node (ref "U1") (pin "5") (pinfunction "DI(IO0)_5") (pintype "bidirectional"))
      (node (ref "U2") (pin "7") (pinfunction "IO7_7") (pintype "bidirectional"))
    )
    (net (code "23") (name "N$17") (class "Default")
      (node (ref "SENSOR2") (pin "2") (pinfunction "CSB_2") (pintype "input"))
      (node (ref "SENSOR2") (pin "6") (pinfunction "VDDIO_6") (pintype "power_in"))
      (node (ref "SENSOR2") (pin "8") (pinfunction "VDD_8") (pintype "power_in"))
    )
    (net (code "24") (name "Net-(CHG_LED-PadC)") (class "Default")
      (node (ref "CHG_LED") (pin "C") (pinfunction "C_C") (pintype "passive"))
      (node (ref "R1_BAT") (pin "2") (pinfunction "2_2") (pintype "passive"))
    )
    (net (code "25") (name "Net-(D2-CATHODE)") (class "Default")
      (node (ref "C1_BAT1") (pin "1") (pinfunction "1_1") (pintype "passive"))
      (node (ref "D2") (pin "1") (pinfunction "CATHODE_1") (pintype "bidirectional"))
      (node (ref "IC4") (pin "1") (pinfunction "VIN_1") (pintype "bidirectional"))
      (node (ref "IC4") (pin "3") (pinfunction "CE_3") (pintype "bidirectional"))
      (node (ref "Q1") (pin "2") (pinfunction "S_2") (pintype "bidirectional"))
    )
    (net (code "26") (name "Net-(D3-A)") (class "Default")
      (node (ref "C4") (pin "1") (pinfunction "1_1") (pintype "passive"))
      (node (ref "D3") (pin "2") (pinfunction "A_2") (pintype "bidirectional"))
      (node (ref "D4") (pin "1") (pinfunction "K_1") (pintype "bidirectional"))
    )
    (net (code "27") (name "Net-(D7-CATHODE)") (class "Default")
      (node (ref "D7") (pin "1") (pinfunction "CATHODE_1") (pintype "bidirectional"))
      (node (ref "R_CAPACITOR") (pin "2") (pinfunction "2_2") (pintype "passive"))
    )
    (net (code "28") (name "Net-(EPD_C1-Pad2)") (class "Default")
      (node (ref "EPD_C1") (pin "2") (pinfunction "2_2") (pintype "passive"))
      (node (ref "J1") (pin "4") (pinfunction "4_4") (pintype "bidirectional"))
    )
    (net (code "29") (name "Net-(EPD_C2-Pad2)") (class "Default")
      (node (ref "EPD_C2") (pin "2") (pinfunction "2_2") (pintype "passive"))
      (node (ref "J1") (pin "5") (pinfunction "5_5") (pintype "bidirectional"))
    )
    (net (code "30") (name "Net-(EPD_C6-Pad2)") (class "Default")
      (node (ref "EPD_C6") (pin "2") (pinfunction "2_2") (pintype "passive"))
      (node (ref "J1") (pin "18") (pinfunction "18_18") (pintype "bidirectional"))
    )
    (net (code "31") (name "Net-(EPD_C7-Pad2)") (class "Default")
      (node (ref "EPD_C7") (pin "2") (pinfunction "2_2") (pintype "passive"))
      (node (ref "J1") (pin "19") (pinfunction "19_19") (pintype "bidirectional"))
    )
    (net (code "32") (name "Net-(EPD_C8-Pad2)") (class "Default")
      (node (ref "EPD_C8") (pin "2") (pinfunction "2_2") (pintype "passive"))
      (node (ref "J1") (pin "20") (pinfunction "20_20") (pintype "bidirectional"))
    )
    (net (code "33") (name "Net-(EPD_C10-Pad2)") (class "Default")
      (node (ref "EPD_C10") (pin "2") (pinfunction "2_2") (pintype "passive"))
      (node (ref "J1") (pin "22") (pinfunction "22_22") (pintype "bidirectional"))
    )
    (net (code "34") (name "Net-(EPD_C12-Pad2)") (class "Default")
      (node (ref "EPD_C12") (pin "2") (pinfunction "2_2") (pintype "passive"))
      (node (ref "J1") (pin "24") (pinfunction "24_24") (pintype "bidirectional"))
    )
    (net (code "35") (name "Net-(IC1-CT)") (class "Default")
      (node (ref "C_DELAY") (pin "1") (pinfunction "1_1") (pintype "passive"))
      (node (ref "IC1") (pin "5") (pinfunction "CT_5") (pintype "bidirectional"))
    )
    (net (code "36") (name "Net-(J2-PadA5)") (class "Default")
      (node (ref "J2") (pin "A5") (pinfunction "A5_A5") (pintype "bidirectional"))
      (node (ref "R2-USB1") (pin "2") (pinfunction "2_2") (pintype "passive"))
    )
    (net (code "37") (name "Net-(J2-PadB5)") (class "Default")
      (node (ref "J2") (pin "B5") (pinfunction "B5_B5") (pintype "bidirectional"))
      (node (ref "R2-USB") (pin "1") (pinfunction "1_1") (pintype "passive"))
    )
    (net (code "38") (name "Net-(MCP73831-PROG)") (class "Default")
      (node (ref "MCP73831") (pin "5") (pinfunction "PROG_5") (pintype "input"))
      (node (ref "R2_BAT") (pin "2") (pinfunction "2_2") (pintype "passive"))
    )
    (net (code "39") (name "Net-(MCP73831-STAT)") (class "Default")
      (node (ref "MCP73831") (pin "1") (pinfunction "STAT_1") (pintype "output"))
      (node (ref "R1_BAT") (pin "1") (pinfunction "1_1") (pintype "passive"))
    )
    (net (code "40") (name "PREVGH") (class "Default")
      (node (ref "D5") (pin "1") (pinfunction "K_1") (pintype "bidirectional"))
      (node (ref "EPD_C9") (pin "2") (pinfunction "2_2") (pintype "passive"))
      (node (ref "J1") (pin "21") (pinfunction "21_21") (pintype "bidirectional"))
    )
    (net (code "41") (name "PREVGL") (class "Default")
      (node (ref "D4") (pin "2") (pinfunction "A_2") (pintype "bidirectional"))
      (node (ref "EPD_C11") (pin "2") (pinfunction "2_2") (pintype "passive"))
      (node (ref "J1") (pin "23") (pinfunction "23_23") (pintype "bidirectional"))
    )
    (net (code "42") (name "RESE") (class "Default")
      (node (ref "J1") (pin "3") (pinfunction "3_3") (pintype "bidirectional"))
      (node (ref "Q3") (pin "2") (pinfunction "S_2") (pintype "bidirectional"))
      (node (ref "R3") (pin "1") (pinfunction "1_1") (pintype "passive"))
    )
    (net (code "43") (name "RESE'") (class "Default")
      (node (ref "R2") (pin "2") (pinfunction "2_2") (pintype "passive"))
      (node (ref "R3") (pin "2") (pinfunction "2_2") (pintype "passive"))
      (node (ref "SJ1") (pin "2") (pinfunction "2_2") (pintype "passive"))
    )
    (net (code "44") (name "RESET") (class "Default")
      (node (ref "C5") (pin "1") (pinfunction "1_1") (pintype "passive"))
      (node (ref "IC1") (pin "1") (pinfunction "VOUT_1") (pintype "bidirectional"))
      (node (ref "RESET_BUTTON") (pin "3") (pinfunction "3_3") (pintype "passive"))
      (node (ref "RESET_BUTTON") (pin "4") (pinfunction "4_4") (pintype "passive"))
      (node (ref "R_RESET") (pin "1") (pinfunction "1_1") (pintype "passive"))
      (node (ref "U2") (pin "3") (pinfunction "EN_3") (pintype "input"))
    )
    (net (code "45") (name "RTC_RST") (class "Default")
      (node (ref "U2") (pin "16") (pinfunction "IO18_16") (pintype "bidirectional"))
      (node (ref "U3") (pin "4") (pinfunction "~{RST}_4") (pintype "input"))
    )
    (net (code "46") (name "RX") (class "Default")
      (node (ref "TP2") (pin "TP") (pinfunction "TP_TP") (pintype "input"))
      (node (ref "U2") (pin "24") (pinfunction "RXD0/GPIO17_24") (pintype "bidirectional"))
    )
    (net (code "47") (name "SCK") (class "Default")
      (node (ref "D10") (pin "1") (pinfunction "1_1") (pintype "passive"))
      (node (ref "J1") (pin "13") (pinfunction "13_13") (pintype "bidirectional"))
      (node (ref "J4") (pin "P5") (pinfunction "CLK_P5") (pintype "bidirectional"))
      (node (ref "R6") (pin "1") (pinfunction "1_1") (pintype "passive"))
      (node (ref "TP8") (pin "TP") (pinfunction "TP_TP") (pintype "input"))
      (node (ref "U1") (pin "6") (pinfunction "CLK_6") (pintype "input"))
      (node (ref "U2") (pin "6") (pinfunction "IO6_6") (pintype "bidirectional"))
    )
    (net (code "48") (name "SCL") (class "Default")
      (node (ref "J3") (pin "4") (pinfunction "4_4") (pintype "passive"))
      (node (ref "R2-PINH") (pin "1") (pinfunction "1_1") (pintype "passive"))
      (node (ref "SENSOR2") (pin "4") (pinfunction "SCK_4") (pintype "input"))
      (node (ref "U2") (pin "20") (pinfunction "IO22_20") (pintype "bidirectional"))
      (node (ref "U3") (pin "16") (pinfunction "SCL_16") (pintype "input"))
      (node (ref "U4") (pin "7") (pinfunction "SCL_7") (pintype "input"))
    )
    (net (code "49") (name "SDA") (class "Default")
      (node (ref "J3") (pin "3") (pinfunction "3_3") (pintype "passive"))
      (node (ref "R1_PINH") (pin "1") (pinfunction "1_1") (pintype "passive"))
      (node (ref "SENSOR2") (pin "3") (pinfunction "SDI_3") (pintype "bidirectional"))
      (node (ref "U2") (pin "19") (pinfunction "IO21_19") (pintype "bidirectional"))
      (node (ref "U3") (pin "15") (pinfunction "SDA_15") (pintype "bidirectional"))
      (node (ref "U4") (pin "8") (pinfunction "SDA_8") (pintype "bidirectional"))
    )
    (net (code "50") (name "SRC") (class "Default")
      (node (ref "C4") (pin "2") (pinfunction "2_2") (pintype "passive"))
      (node (ref "D5") (pin "2") (pinfunction "A_2") (pintype "bidirectional"))
      (node (ref "L1") (pin "1") (pinfunction "1_1") (pintype "passive"))
      (node (ref "Q3") (pin "3") (pinfunction "D_3") (pintype "bidirectional"))
    )
    (net (code "51") (name "SS_SD") (class "Default")
      (node (ref "D6") (pin "1") (pinfunction "1_1") (pintype "passive"))
      (node (ref "J4") (pin "P2") (pinfunction "CD/DAT3_P2") (pintype "bidirectional"))
      (node (ref "R10") (pin "1") (pinfunction "1_1") (pintype "passive"))
      (node (ref "U2") (pin "4") (pinfunction "IO4_4") (pintype "bidirectional"))
    )
    (net (code "52") (name "TX") (class "Default")
      (node (ref "TP1") (pin "TP") (pinfunction "TP_TP") (pintype "input"))
      (node (ref "U2") (pin "25") (pinfunction "TXD0/GPIO16_25") (pintype "bidirectional"))
    )
    (net (code "53") (name "USB_D+") (class "Default")
      (node (ref "D1") (pin "3") (pinfunction "I/O2_1_3") (pintype "bidirectional"))
      (node (ref "U2") (pin "14") (pinfunction "IO13_14") (pintype "bidirectional"))
    )
    (net (code "54") (name "USB_D-") (class "Default")
      (node (ref "D1") (pin "1") (pinfunction "I/O1_1_1") (pintype "bidirectional"))
      (node (ref "U2") (pin "13") (pinfunction "IO12_13") (pintype "bidirectional"))
    )
    (net (code "55") (name "VBAT") (class "Default")
      (node (ref "C2_BAT") (pin "1") (pinfunction "1_1") (pintype "passive"))
      (node (ref "MCP73831") (pin "3") (pinfunction "VBAT_3") (pintype "power_in"))
      (node (ref "Q1") (pin "3") (pinfunction "D_3") (pintype "bidirectional"))
      (node (ref "TP3") (pin "TP") (pinfunction "TP_TP") (pintype "input"))
      (node (ref "U4") (pin "2") (pinfunction "CELL_2") (pintype "power_in"))
      (node (ref "U4") (pin "3") (pinfunction "VDD_3") (pintype "power_in"))
    )
    (net (code "56") (name "VBUS") (class "Default")
      (node (ref "C1_BAT") (pin "1") (pinfunction "1_1") (pintype "passive"))
      (node (ref "C4_USB") (pin "1") (pinfunction "1_1") (pintype "passive"))
      (node (ref "C5_USB") (pin "1") (pinfunction "1_1") (pintype "passive"))
      (node (ref "CHG_LED") (pin "A") (pinfunction "A_A") (pintype "passive"))
      (node (ref "D1") (pin "5") (pinfunction "VBUS_5") (pintype "bidirectional"))
      (node (ref "D2") (pin "2") (pinfunction "ANODE_2") (pintype "bidirectional"))
      (node (ref "MCP73831") (pin "4") (pinfunction "VIN_4") (pintype "power_in"))
      (node (ref "PFMF.050.1") (pin "2") (pinfunction "2_2") (pintype "passive"))
      (node (ref "Q1") (pin "1") (pinfunction "G_1") (pintype "bidirectional"))
      (node (ref "R1_PWRUSB") (pin "2") (pinfunction "2_2") (pintype "passive"))
      (node (ref "TP14") (pin "TP") (pinfunction "TP_TP") (pintype "input"))
    )
    (net (code "57") (name "VRTC") (class "Default")
      (node (ref "C10_SUPERCAP") (pin "2") (pinfunction "2_2") (pintype "passive"))
      (node (ref "C8") (pin "1") (pinfunction "1_1") (pintype "passive"))
      (node (ref "R_CAPACITOR") (pin "1") (pinfunction "1_1") (pintype "passive"))
      (node (ref "U3") (pin "14") (pinfunction "VBAT_14") (pintype "power_in"))
    )
    (net (code "58") (name "VUSB") (class "Default")
      (node (ref "J2") (pin "A4") (pinfunction "A4_A4") (pintype "bidirectional"))
      (node (ref "J2") (pin "A9") (pinfunction "A9_A9") (pintype "bidirectional"))
      (node (ref "J2") (pin "B4") (pinfunction "B4_B4") (pintype "bidirectional"))
      (node (ref "J2") (pin "B9") (pinfunction "B9_B9") (pintype "bidirectional"))
      (node (ref "PFMF.050.1") (pin "1") (pinfunction "1_1") (pintype "passive"))
    )
    (net (code "59") (name "unconnected-(IC1-NC-Pad4)") (class "Default")
      (node (ref "IC1") (pin "4") (pinfunction "NC_4") (pintype "no_connect"))
    )
    (net (code "60") (name "unconnected-(IC1-VDD-Pad2)") (class "Default")
      (node (ref "IC1") (pin "2") (pinfunction "VDD_2") (pintype "bidirectional"))
    )
    (net (code "61") (name "unconnected-(IC4-NC-Pad4)") (class "Default")
      (node (ref "IC4") (pin "4") (pinfunction "NC_4") (pintype "no_connect"))
    )
    (net (code "62") (name "unconnected-(J1-Pad1)") (class "Default")
      (node (ref "J1") (pin "1") (pinfunction "1_1") (pintype "bidirectional"))
    )
    (net (code "63") (name "unconnected-(J1-Pad6)") (class "Default")
      (node (ref "J1") (pin "6") (pinfunction "6_6") (pintype "bidirectional"))
    )
    (net (code "64") (name "unconnected-(J1-Pad7)") (class "Default")
      (node (ref "J1") (pin "7") (pinfunction "7_7") (pintype "bidirectional"))
    )
    (net (code "65") (name "unconnected-(J2-PadA8)") (class "Default")
      (node (ref "J2") (pin "A8") (pinfunction "A8_A8") (pintype "bidirectional"))
    )
    (net (code "66") (name "unconnected-(J2-PadB8)") (class "Default")
      (node (ref "J2") (pin "B8") (pinfunction "B8_B8") (pintype "bidirectional"))
    )
    (net (code "67") (name "unconnected-(J4-DAT1-PadP8)") (class "Default")
      (node (ref "J4") (pin "P8") (pinfunction "DAT1_P8") (pintype "bidirectional"))
    )
    (net (code "68") (name "unconnected-(J4-DAT2-PadP1)") (class "Default")
      (node (ref "J4") (pin "P1") (pinfunction "DAT2_P1") (pintype "bidirectional"))
    )
    (net (code "69") (name "unconnected-(J4-DETECTION_1-PadS1)") (class "Default")
      (node (ref "J4") (pin "S1") (pinfunction "DETECTION_1_S1") (pintype "bidirectional"))
    )
    (net (code "70") (name "unconnected-(J4-DETECTION_2-PadS2)") (class "Default")
      (node (ref "J4") (pin "S2") (pinfunction "DETECTION_2_S2") (pintype "bidirectional"))
    )
    (net (code "71") (name "unconnected-(U2-NC-Pad22)") (class "Default")
      (node (ref "U2") (pin "22") (pinfunction "NC_22") (pintype "no_connect"))
    )
    (net (code "72") (name "unconnected-(U4-~{ALERT}-Pad5)") (class "Default")
      (node (ref "U4") (pin "5") (pinfunction "~{ALERT}_5") (pintype "output"))
    )
  )
)
